# CSR8675_Module_Bluetooth_Speaker.net
KiCad netlist of a schematic drawn in EasyEDA Pro
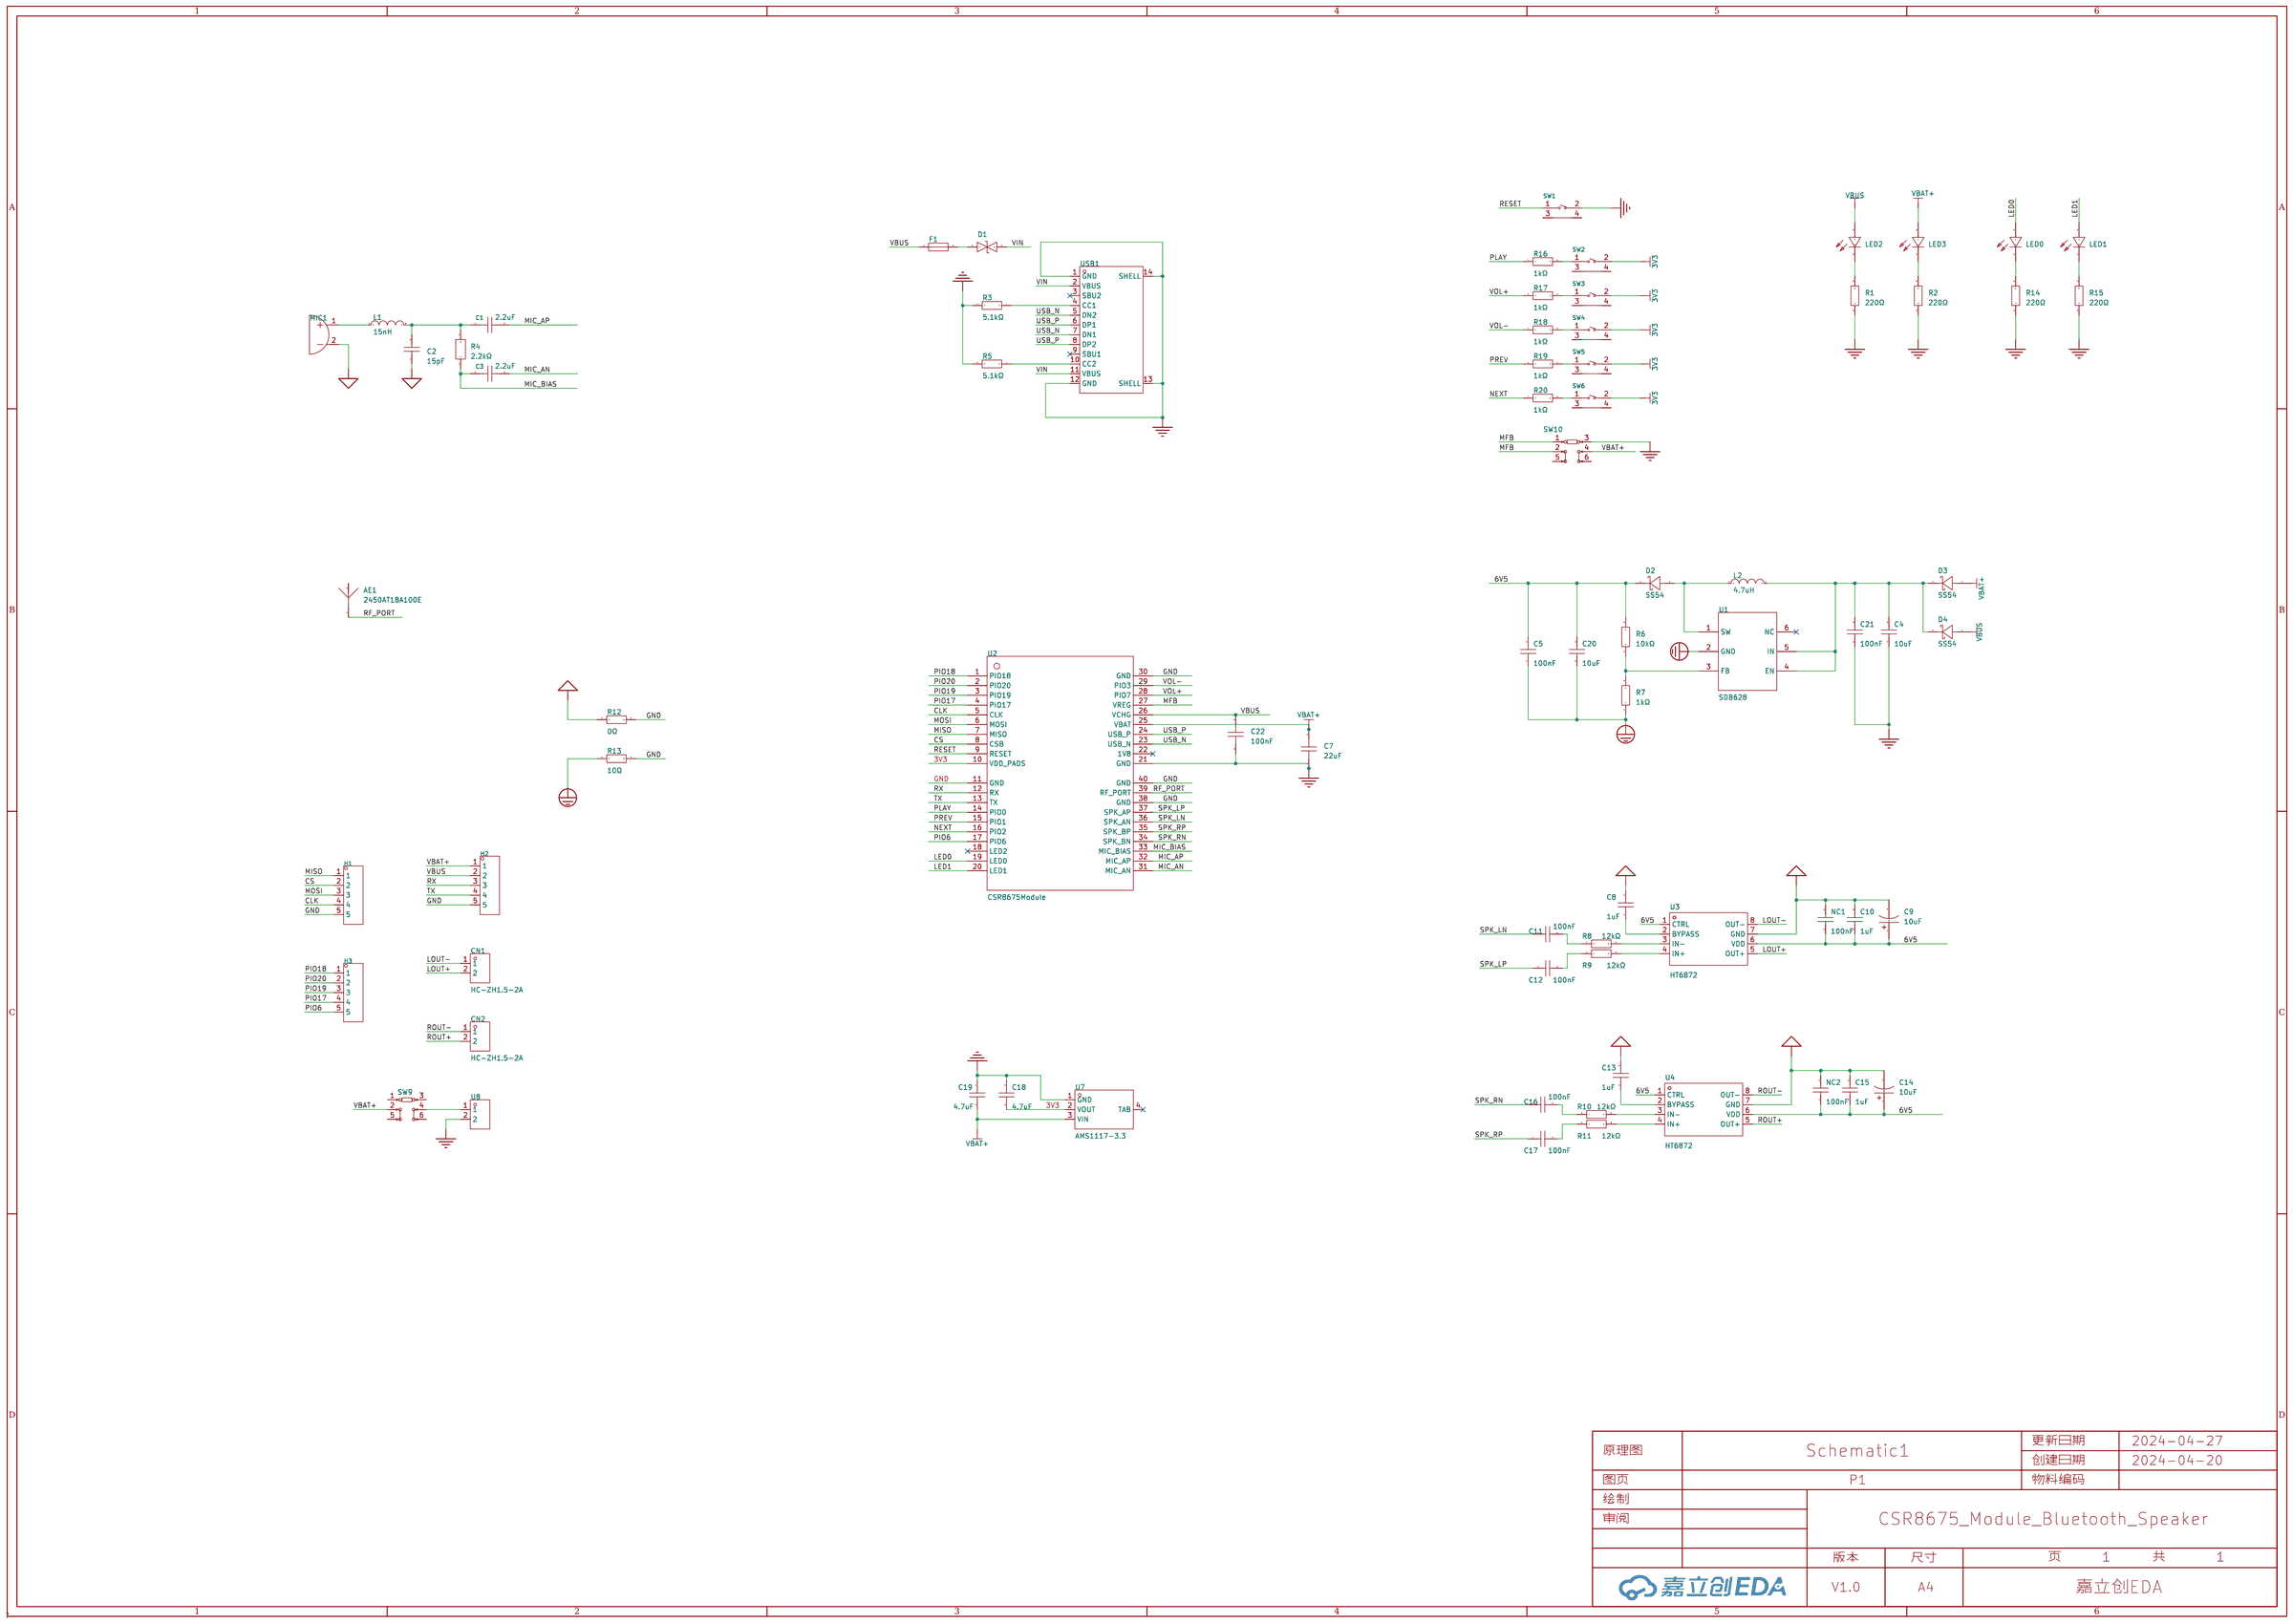
[diagram p0: schematic sheet]

(export (version "E")
  (design (tool "Eeschema 10.0.6"))
  (components
    (comp (ref "AE1")
      (value "2450AT18A100E")
      (footprint "easyedapro:ANT-SMD_L3.2-W1.6")
      (description "天线类型:2.4G天线;中心频点:2.4GHz;带宽:-;峰值增益:0.5dBi;极化方式:-;功率容量:2W;驻波比:-;")
      (fields (field (name "Manufacturer") "JOHANSON(约翰逊)"))
      (libsource (lib "easyedapro") (part "2450AT18A100E"))
    )
    (comp (ref "C1")
      (value "2.2uF")
      (footprint "easyedapro:C0603")
      (description "容值:2.2uF;精度:±10%;额定电压:50V;材质(温度系数):X5R;")
      (fields
        (field (name "Manufacturer Part") "CL10A225KB8NNNC")
        (field (name "Manufacturer") "SAMSUNG(三星)")
      )
      (libsource (lib "easyedapro") (part "CL10A225KB8NNNC"))
    )
    (comp (ref "C2")
      (value "15pF")
      (footprint "easyedapro:C0603")
      (description "容值:15pF;精度:±5%;额定电压:50V;材质(温度系数):NP0;")
      (fields
        (field (name "Manufacturer Part") "CC0603JRNPO9BN150")
        (field (name "Manufacturer") "YAGEO(国巨)")
      )
      (libsource (lib "easyedapro") (part "CC0603JRNPO9BN150"))
    )
    (comp (ref "C3")
      (value "2.2uF")
      (footprint "easyedapro:C0603")
      (description "容值:2.2uF;精度:±10%;额定电压:50V;材质(温度系数):X5R;")
      (fields
        (field (name "Manufacturer Part") "CL10A225KB8NNNC")
        (field (name "Manufacturer") "SAMSUNG(三星)")
      )
      (libsource (lib "easyedapro") (part "CL10A225KB8NNNC"))
    )
    (comp (ref "C4")
      (value "10uF")
      (footprint "easyedapro:C0603")
      (description "容值:1uF;精度:±10%;额定电压:50V;材质(温度系数):X5R;")
      (fields
        (field (name "Manufacturer Part") "CL10A105KB8NNNC")
        (field (name "Manufacturer") "SAMSUNG(三星)")
      )
      (libsource (lib "easyedapro") (part "CL10A105KB8NNNC"))
    )
    (comp (ref "C5")
      (value "100nF")
      (footprint "easyedapro:C0603")
      (description "容值:1uF;精度:±10%;额定电压:50V;材质(温度系数):X5R;")
      (fields
        (field (name "Manufacturer Part") "CL10A105KB8NNNC")
        (field (name "Manufacturer") "SAMSUNG(三星)")
      )
      (libsource (lib "easyedapro") (part "CL10A105KB8NNNC"))
    )
    (comp (ref "C7")
      (value "22uF")
      (footprint "easyedapro:c0805")
      (description "容值:22uF;精度:±20%;额定电压:25V;材质(温度系数):X5R;")
      (fields
        (field (name "Manufacturer Part") "CL21A226MAQNNNE")
        (field (name "Manufacturer") "SAMSUNG(三星)")
      )
      (libsource (lib "easyedapro") (part "CL21A226MAQNNNE"))
    )
    (comp (ref "C8")
      (value "1uF")
      (footprint "easyedapro:C0603")
      (description "容值:1uF;精度:±10%;额定电压:50V;材质(温度系数):X5R;")
      (fields
        (field (name "Manufacturer Part") "CL10A105KB8NNNC")
        (field (name "Manufacturer") "SAMSUNG(三星)")
      )
      (libsource (lib "easyedapro") (part "CL10A105KB8NNNC"))
    )
    (comp (ref "C9")
      (value "10uF")
      (footprint "easyedapro:CAP-TH_BD5.0-P2.00-D0.8-FD")
      (description "容值:10uF;精度:±20%;额定电压:50V;纹波电流:50mA@120Hz;等效串联电阻:-;")
      (fields
        (field (name "Manufacturer Part") "01EC1809SHC10UF50V")
        (field (name "Manufacturer") "KNSCHA(科尼盛)")
      )
      (libsource (lib "easyedapro") (part "01EC1809SHC10UF50V"))
    )
    (comp (ref "C10")
      (value "1uF")
      (footprint "easyedapro:C0603")
      (description "容值:1uF;精度:±10%;额定电压:50V;材质(温度系数):X5R;")
      (fields
        (field (name "Manufacturer Part") "CL10A105KB8NNNC")
        (field (name "Manufacturer") "SAMSUNG(三星)")
      )
      (libsource (lib "easyedapro") (part "CL10A105KB8NNNC"))
    )
    (comp (ref "C11")
      (value "100nF")
      (footprint "easyedapro:C0603")
      (description "容值:100nF;精度:±10%;额定电压:50V;材质(温度系数):X7R;")
      (fields (field (name "Manufacturer Part") "0603B104K500NT") (field (name "Manufacturer") "FH(风华)"))
      (libsource (lib "easyedapro") (part "0603B104K500NT"))
    )
    (comp (ref "C12")
      (value "100nF")
      (footprint "easyedapro:C0603")
      (description "容值:100nF;精度:±10%;额定电压:50V;材质(温度系数):X7R;")
      (fields (field (name "Manufacturer Part") "0603B104K500NT") (field (name "Manufacturer") "FH(风华)"))
      (libsource (lib "easyedapro") (part "0603B104K500NT"))
    )
    (comp (ref "C13")
      (value "1uF")
      (footprint "easyedapro:C0603")
      (description "容值:1uF;精度:±10%;额定电压:50V;材质(温度系数):X5R;")
      (fields
        (field (name "Manufacturer Part") "CL10A105KB8NNNC")
        (field (name "Manufacturer") "SAMSUNG(三星)")
      )
      (libsource (lib "easyedapro") (part "CL10A105KB8NNNC"))
    )
    (comp (ref "C14")
      (value "10uF")
      (footprint "easyedapro:CAP-TH_BD5.0-P2.00-D0.8-FD")
      (description "容值:10uF;精度:±20%;额定电压:50V;纹波电流:50mA@120Hz;等效串联电阻:-;")
      (fields
        (field (name "Manufacturer Part") "01EC1809SHC10UF50V")
        (field (name "Manufacturer") "KNSCHA(科尼盛)")
      )
      (libsource (lib "easyedapro") (part "01EC1809SHC10UF50V"))
    )
    (comp (ref "C15")
      (value "1uF")
      (footprint "easyedapro:C0603")
      (description "容值:1uF;精度:±10%;额定电压:50V;材质(温度系数):X5R;")
      (fields
        (field (name "Manufacturer Part") "CL10A105KB8NNNC")
        (field (name "Manufacturer") "SAMSUNG(三星)")
      )
      (libsource (lib "easyedapro") (part "CL10A105KB8NNNC"))
    )
    (comp (ref "C16")
      (value "100nF")
      (footprint "easyedapro:C0603")
      (description "容值:100nF;精度:±10%;额定电压:50V;材质(温度系数):X7R;")
      (fields (field (name "Manufacturer Part") "0603B104K500NT") (field (name "Manufacturer") "FH(风华)"))
      (libsource (lib "easyedapro") (part "0603B104K500NT"))
    )
    (comp (ref "C17")
      (value "100nF")
      (footprint "easyedapro:C0603")
      (description "容值:100nF;精度:±10%;额定电压:50V;材质(温度系数):X7R;")
      (fields (field (name "Manufacturer Part") "0603B104K500NT") (field (name "Manufacturer") "FH(风华)"))
      (libsource (lib "easyedapro") (part "0603B104K500NT"))
    )
    (comp (ref "C18")
      (value "4.7uF")
      (footprint "easyedapro:c0805")
      (description "容值:4.7uF;精度:±10%;额定电压:25V;材质(温度系数):X5R;")
      (fields
        (field (name "Manufacturer Part") "CL21A475KAQNNNE")
        (field (name "Manufacturer") "SAMSUNG(三星)")
      )
      (libsource (lib "easyedapro") (part "CL21A475KAQNNNE"))
    )
    (comp (ref "C19")
      (value "4.7uF")
      (footprint "easyedapro:c0805")
      (description "容值:4.7uF;精度:±10%;额定电压:25V;材质(温度系数):X5R;")
      (fields
        (field (name "Manufacturer Part") "CL21A475KAQNNNE")
        (field (name "Manufacturer") "SAMSUNG(三星)")
      )
      (libsource (lib "easyedapro") (part "CL21A475KAQNNNE"))
    )
    (comp (ref "C20")
      (value "10uF")
      (footprint "easyedapro:C0603")
      (description "容值:1uF;精度:±10%;额定电压:50V;材质(温度系数):X5R;")
      (fields
        (field (name "Manufacturer Part") "CL10A105KB8NNNC")
        (field (name "Manufacturer") "SAMSUNG(三星)")
      )
      (libsource (lib "easyedapro") (part "CL10A105KB8NNNC"))
    )
    (comp (ref "C21")
      (value "100nF")
      (footprint "easyedapro:C0603")
      (description "容值:1uF;精度:±10%;额定电压:50V;材质(温度系数):X5R;")
      (fields
        (field (name "Manufacturer Part") "CL10A105KB8NNNC")
        (field (name "Manufacturer") "SAMSUNG(三星)")
      )
      (libsource (lib "easyedapro") (part "CL10A105KB8NNNC"))
    )
    (comp (ref "C22")
      (value "100nF")
      (footprint "easyedapro:C0603")
      (description "容值:100nF;精度:±10%;额定电压:50V;材质(温度系数):X7R;")
      (fields
        (field (name "Manufacturer Part") "CC0603KRX7R9BB104")
        (field (name "Manufacturer") "YAGEO(国巨)")
      )
      (libsource (lib "easyedapro") (part "CC0603KRX7R9BB104"))
    )
    (comp (ref "CN1")
      (value "HC-ZH1.5-2A")
      (footprint "easyedapro:CONN-TH_2P-P1.50_HCTL_HC-ZH1.5-2A")
      (fields (field (name "Manufacturer") "HCTL(华灿天禄)"))
      (libsource (lib "easyedapro") (part "HC-ZH1.5-2A"))
    )
    (comp (ref "CN2")
      (value "HC-ZH1.5-2A")
      (footprint "easyedapro:CONN-TH_2P-P1.50_HCTL_HC-ZH1.5-2A")
      (fields (field (name "Manufacturer") "HCTL(华灿天禄)"))
      (libsource (lib "easyedapro") (part "HC-ZH1.5-2A"))
    )
    (comp (ref "D1")
      (value "0603ESDA-05N")
      (footprint "easyedapro:D0603-BI")
      (description "极性:双向;反向截止电压(Vrwm):5V;最大钳位电压:50V;")
      (fields (field (name "Manufacturer") "BORN(伯恩半导体)"))
      (libsource (lib "easyedapro") (part "0603ESDA-05N"))
    )
    (comp (ref "D2")
      (value "SS54")
      (footprint "easyedapro:SMA_L4.3-W2.6-LS5.0-FD")
      (description "二极管配置:独立式;正向压降(Vf):550mV@5.0A;直流反向耐压(Vr):40V;平均整流电流(Io):5A;")
      (fields (field (name "Manufacturer") "宏迦橙"))
      (libsource (lib "easyedapro") (part "SS54_C7420369"))
    )
    (comp (ref "D3")
      (value "SS54")
      (footprint "easyedapro:SMA_L4.3-W2.6-LS5.0-FD")
      (description "二极管配置:独立式;正向压降(Vf):550mV@5.0A;直流反向耐压(Vr):40V;平均整流电流(Io):5A;")
      (fields (field (name "Manufacturer") "宏迦橙"))
      (libsource (lib "easyedapro") (part "SS54_C7420369"))
    )
    (comp (ref "D4")
      (value "SS54")
      (footprint "easyedapro:SMA_L4.3-W2.6-LS5.0-FD")
      (description "二极管配置:独立式;正向压降(Vf):550mV@5.0A;直流反向耐压(Vr):40V;平均整流电流(Io):5A;")
      (fields (field (name "Manufacturer") "宏迦橙"))
      (libsource (lib "easyedapro") (part "SS54_C7420369"))
    )
    (comp (ref "F1")
      (value "BSMD1210L-500")
      (footprint "easyedapro:F1210")
      (description "最大电压:6V;最大电流:50A;保持电流:5A;跳闸电流:10A;")
      (fields (field (name "Manufacturer") "BHFUSE(佰宏)"))
      (libsource (lib "easyedapro") (part "BSMD1210L-500"))
    )
    (comp (ref "H1")
      (value "~")
      (footprint "easyedapro:HDR-TH_5P-P2.54-V-M")
      (libsource (lib "easyedapro") (part "MTP125-1105S1"))
    )
    (comp (ref "H2")
      (value "~")
      (footprint "easyedapro:HDR-TH_5P-P2.54-V-M")
      (libsource (lib "easyedapro") (part "MTP125-1105S1"))
    )
    (comp (ref "H3")
      (value "~")
      (footprint "easyedapro:HDR-TH_5P-P2.54-V-M")
      (libsource (lib "easyedapro") (part "MTP125-1105S1"))
    )
    (comp (ref "L1")
      (value "15nH")
      (footprint "easyedapro:L0805")
      (description "电感值:15nH;精度:±5%;额定电流:300mA;饱和电流(Isat):-;直流电阻(DCR):400mΩ;")
      (fields (field (name "Manufacturer Part") "VHF201209H15NJT") (field (name "Manufacturer") "FH(风华)"))
      (libsource (lib "easyedapro") (part "VHF201209H15NJT"))
    )
    (comp (ref "L2")
      (value "4.7uH")
      (footprint "easyedapro:IND-SMD_L4.4-W4.2")
      (description "电感值:4.7uH;精度:±20%;额定电流:2.8A;饱和电流(Isat):3A;类型:一体成型电感;")
      (fields (field (name "Manufacturer Part") "FXL0420-4R7-M") (field (name "Manufacturer") "cjiang(长江微电)"))
      (libsource (lib "easyedapro") (part "FXL0420-4R7-M"))
    )
    (comp (ref "LED0")
      (value "NCD0603R1")
      (footprint "easyedapro:LED0603-RD_RED")
      (fields (field (name "Manufacturer") "国星光电"))
      (libsource (lib "easyedapro") (part "FC-DA1608HRK-620D"))
    )
    (comp (ref "LED1")
      (value "NCD0603R1")
      (footprint "easyedapro:LED0603-RD_RED")
      (fields (field (name "Manufacturer") "国星光电"))
      (libsource (lib "easyedapro") (part "FC-DA1608HRK-620D"))
    )
    (comp (ref "LED2")
      (value "NCD0603R1")
      (footprint "easyedapro:LED0603-RD_RED")
      (fields (field (name "Manufacturer") "国星光电"))
      (libsource (lib "easyedapro") (part "FC-DA1608HRK-620D"))
    )
    (comp (ref "LED3")
      (value "NCD0603R1")
      (footprint "easyedapro:LED0603-RD_RED")
      (fields (field (name "Manufacturer") "国星光电"))
      (libsource (lib "easyedapro") (part "FC-DA1608HRK-620D"))
    )
    (comp (ref "MIC1")
      (value "GMI6027P-34DB")
      (footprint "easyedapro:MIC-TH_BD6.0-P1.90-D0.4-L")
      (fields (field (name "Manufacturer") "INGHAi(赢海)"))
      (libsource (lib "easyedapro") (part "GMI6027P-34DB"))
    )
    (comp (ref "NC1")
      (value "100nF")
      (footprint "easyedapro:C0603")
      (description "容值:10nF;精度:±10%;额定电压:50V;材质(温度系数):X7R;")
      (fields
        (field (name "Manufacturer Part") "CC0603KRX7R9BB103")
        (field (name "Manufacturer") "YAGEO(国巨)")
      )
      (libsource (lib "easyedapro") (part "CC0603KRX7R9BB103"))
    )
    (comp (ref "NC2")
      (value "100nF")
      (footprint "easyedapro:C0603")
      (description "容值:10nF;精度:±10%;额定电压:50V;材质(温度系数):X7R;")
      (fields
        (field (name "Manufacturer Part") "CC0603KRX7R9BB103")
        (field (name "Manufacturer") "YAGEO(国巨)")
      )
      (libsource (lib "easyedapro") (part "CC0603KRX7R9BB103"))
    )
    (comp (ref "R1")
      (value "220Ω")
      (footprint "easyedapro:R0603")
      (description "电阻类型:厚膜电阻;阻值:220Ω;精度:±5%;功率:100mW;最大工作电压:75V;温度系数:±100ppm/°C;")
      (fields
        (field (name "Manufacturer Part") "0603WAJ0221T5E")
        (field (name "Manufacturer") "UNI-ROYAL(厚声)")
      )
      (libsource (lib "easyedapro") (part "0603WAJ0221T5E"))
    )
    (comp (ref "R2")
      (value "220Ω")
      (footprint "easyedapro:R0603")
      (description "电阻类型:厚膜电阻;阻值:220Ω;精度:±5%;功率:100mW;最大工作电压:75V;温度系数:±100ppm/°C;")
      (fields
        (field (name "Manufacturer Part") "0603WAJ0221T5E")
        (field (name "Manufacturer") "UNI-ROYAL(厚声)")
      )
      (libsource (lib "easyedapro") (part "0603WAJ0221T5E"))
    )
    (comp (ref "R3")
      (value "5.1kΩ")
      (footprint "easyedapro:R0603")
      (description "电阻类型:厚膜电阻;阻值:5.1kΩ;精度:±1%;功率:100mW;最大工作电压:75V;温度系数:±100ppm/°C;")
      (fields
        (field (name "Manufacturer Part") "0603WAF5101T5E")
        (field (name "Manufacturer") "UNI-ROYAL(厚声)")
      )
      (libsource (lib "easyedapro") (part "0603WAF5101T5E"))
    )
    (comp (ref "R4")
      (value "2.2kΩ")
      (footprint "easyedapro:R0603")
      (description "电阻类型:厚膜电阻;阻值:2.2kΩ;精度:±5%;功率:100mW;最大工作电压:75V;温度系数:±100ppm/°C;")
      (fields (field (name "Manufacturer Part") "FRC0603J222 TS") (field (name "Manufacturer") "FOJAN(富捷)"))
      (libsource (lib "easyedapro") (part "FRC0603J222 TS"))
    )
    (comp (ref "R5")
      (value "5.1kΩ")
      (footprint "easyedapro:R0603")
      (description "电阻类型:厚膜电阻;阻值:5.1kΩ;精度:±1%;功率:100mW;最大工作电压:75V;温度系数:±100ppm/°C;")
      (fields
        (field (name "Manufacturer Part") "0603WAF5101T5E")
        (field (name "Manufacturer") "UNI-ROYAL(厚声)")
      )
      (libsource (lib "easyedapro") (part "0603WAF5101T5E"))
    )
    (comp (ref "R6")
      (value "10kΩ")
      (footprint "easyedapro:R0603")
      (description "电阻类型:厚膜电阻;阻值:10kΩ;精度:±1%;功率:100mW;最大工作电压:75V;温度系数:±100ppm/°C;")
      (fields
        (field (name "Manufacturer Part") "0603WAF1002T5E")
        (field (name "Manufacturer") "UNI-ROYAL(厚声)")
      )
      (libsource (lib "easyedapro") (part "0603WAF1002T5E"))
    )
    (comp (ref "R7")
      (value "1kΩ")
      (footprint "easyedapro:R0603")
      (description "电阻类型:厚膜电阻;阻值:1kΩ;精度:±1%;功率:100mW;最大工作电压:75V;温度系数:±100ppm/°C;")
      (fields (field (name "Manufacturer Part") "RC0603FR-071KL") (field (name "Manufacturer") "YAGEO(国巨)"))
      (libsource (lib "easyedapro") (part "RC0603FR-071KL"))
    )
    (comp (ref "R8")
      (value "12kΩ")
      (footprint "easyedapro:R0603")
      (description "电阻类型:厚膜电阻;阻值:12kΩ;精度:±1%;功率:100mW;最大工作电压:75V;温度系数:±100ppm/°C;")
      (fields
        (field (name "Manufacturer Part") "0603WAF1202T5E")
        (field (name "Manufacturer") "UNI-ROYAL(厚声)")
      )
      (libsource (lib "easyedapro") (part "0603WAF1202T5E"))
    )
    (comp (ref "R9")
      (value "12kΩ")
      (footprint "easyedapro:R0603")
      (description "电阻类型:厚膜电阻;阻值:12kΩ;精度:±1%;功率:100mW;最大工作电压:75V;温度系数:±100ppm/°C;")
      (fields
        (field (name "Manufacturer Part") "0603WAF1202T5E")
        (field (name "Manufacturer") "UNI-ROYAL(厚声)")
      )
      (libsource (lib "easyedapro") (part "0603WAF1202T5E"))
    )
    (comp (ref "R10")
      (value "12kΩ")
      (footprint "easyedapro:R0603")
      (description "电阻类型:厚膜电阻;阻值:12kΩ;精度:±1%;功率:100mW;最大工作电压:75V;温度系数:±100ppm/°C;")
      (fields
        (field (name "Manufacturer Part") "0603WAF1202T5E")
        (field (name "Manufacturer") "UNI-ROYAL(厚声)")
      )
      (libsource (lib "easyedapro") (part "0603WAF1202T5E"))
    )
    (comp (ref "R11")
      (value "12kΩ")
      (footprint "easyedapro:R0603")
      (description "电阻类型:厚膜电阻;阻值:12kΩ;精度:±1%;功率:100mW;最大工作电压:75V;温度系数:±100ppm/°C;")
      (fields
        (field (name "Manufacturer Part") "0603WAF1202T5E")
        (field (name "Manufacturer") "UNI-ROYAL(厚声)")
      )
      (libsource (lib "easyedapro") (part "0603WAF1202T5E"))
    )
    (comp (ref "R12")
      (value "0Ω")
      (footprint "easyedapro:R0603")
      (description "电阻类型:厚膜电阻;阻值:0Ω;精度:±1%;功率:100mW;最大工作电压:75V;")
      (fields
        (field (name "Manufacturer Part") "0603WAF0000T5E")
        (field (name "Manufacturer") "UNI-ROYAL(厚声)")
      )
      (libsource (lib "easyedapro") (part "0603WAF0000T5E"))
    )
    (comp (ref "R13")
      (value "10Ω")
      (footprint "easyedapro:R0603")
      (description "电阻类型:厚膜电阻;阻值:0Ω;精度:±1%;功率:100mW;最大工作电压:75V;")
      (fields
        (field (name "Manufacturer Part") "0603WAF0000T5E")
        (field (name "Manufacturer") "UNI-ROYAL(厚声)")
      )
      (libsource (lib "easyedapro") (part "0603WAF0000T5E"))
    )
    (comp (ref "R14")
      (value "220Ω")
      (footprint "easyedapro:R0603")
      (description "电阻类型:厚膜电阻;阻值:220Ω;精度:±5%;功率:100mW;最大工作电压:75V;温度系数:±100ppm/°C;")
      (fields
        (field (name "Manufacturer Part") "0603WAJ0221T5E")
        (field (name "Manufacturer") "UNI-ROYAL(厚声)")
      )
      (libsource (lib "easyedapro") (part "0603WAJ0221T5E"))
    )
    (comp (ref "R15")
      (value "220Ω")
      (footprint "easyedapro:R0603")
      (description "电阻类型:厚膜电阻;阻值:220Ω;精度:±5%;功率:100mW;最大工作电压:75V;温度系数:±100ppm/°C;")
      (fields
        (field (name "Manufacturer Part") "0603WAJ0221T5E")
        (field (name "Manufacturer") "UNI-ROYAL(厚声)")
      )
      (libsource (lib "easyedapro") (part "0603WAJ0221T5E"))
    )
    (comp (ref "R16")
      (value "1kΩ")
      (footprint "easyedapro:R0603")
      (description "电阻类型:厚膜电阻;阻值:1kΩ;精度:±1%;功率:100mW;最大工作电压:75V;温度系数:±100ppm/°C;")
      (fields (field (name "Manufacturer Part") "RC0603FR-071KL") (field (name "Manufacturer") "YAGEO(国巨)"))
      (libsource (lib "easyedapro") (part "RC0603FR-071KL"))
    )
    (comp (ref "R17")
      (value "1kΩ")
      (footprint "easyedapro:R0603")
      (description "电阻类型:厚膜电阻;阻值:1kΩ;精度:±1%;功率:100mW;最大工作电压:75V;温度系数:±100ppm/°C;")
      (fields (field (name "Manufacturer Part") "RC0603FR-071KL") (field (name "Manufacturer") "YAGEO(国巨)"))
      (libsource (lib "easyedapro") (part "RC0603FR-071KL"))
    )
    (comp (ref "R18")
      (value "1kΩ")
      (footprint "easyedapro:R0603")
      (description "电阻类型:厚膜电阻;阻值:1kΩ;精度:±1%;功率:100mW;最大工作电压:75V;温度系数:±100ppm/°C;")
      (fields (field (name "Manufacturer Part") "RC0603FR-071KL") (field (name "Manufacturer") "YAGEO(国巨)"))
      (libsource (lib "easyedapro") (part "RC0603FR-071KL"))
    )
    (comp (ref "R19")
      (value "1kΩ")
      (footprint "easyedapro:R0603")
      (description "电阻类型:厚膜电阻;阻值:1kΩ;精度:±1%;功率:100mW;最大工作电压:75V;温度系数:±100ppm/°C;")
      (fields (field (name "Manufacturer Part") "RC0603FR-071KL") (field (name "Manufacturer") "YAGEO(国巨)"))
      (libsource (lib "easyedapro") (part "RC0603FR-071KL"))
    )
    (comp (ref "R20")
      (value "1kΩ")
      (footprint "easyedapro:R0603")
      (description "电阻类型:厚膜电阻;阻值:1kΩ;精度:±1%;功率:100mW;最大工作电压:75V;温度系数:±100ppm/°C;")
      (fields (field (name "Manufacturer Part") "RC0603FR-071KL") (field (name "Manufacturer") "YAGEO(国巨)"))
      (libsource (lib "easyedapro") (part "RC0603FR-071KL"))
    )
    (comp (ref "SW1")
      (value "TC-6615-5-260G")
      (footprint "easyedapro:SW-TH_4P-L7.5-W5.0-P4.50")
      (fields (field (name "Manufacturer") "HCTL(华灿天禄)"))
      (libsource (lib "easyedapro") (part "TC-6615-5-260G"))
    )
    (comp (ref "SW2")
      (value "TC-6615-5-260G")
      (footprint "easyedapro:SW-TH_4P-L7.5-W5.0-P4.50")
      (fields (field (name "Manufacturer") "HCTL(华灿天禄)"))
      (libsource (lib "easyedapro") (part "TC-6615-5-260G"))
    )
    (comp (ref "SW3")
      (value "TC-6615-5-260G")
      (footprint "easyedapro:SW-TH_4P-L7.5-W5.0-P4.50")
      (fields (field (name "Manufacturer") "HCTL(华灿天禄)"))
      (libsource (lib "easyedapro") (part "TC-6615-5-260G"))
    )
    (comp (ref "SW4")
      (value "TC-6615-5-260G")
      (footprint "easyedapro:SW-TH_4P-L7.5-W5.0-P4.50")
      (fields (field (name "Manufacturer") "HCTL(华灿天禄)"))
      (libsource (lib "easyedapro") (part "TC-6615-5-260G"))
    )
    (comp (ref "SW5")
      (value "TC-6615-5-260G")
      (footprint "easyedapro:SW-TH_4P-L7.5-W5.0-P4.50")
      (fields (field (name "Manufacturer") "HCTL(华灿天禄)"))
      (libsource (lib "easyedapro") (part "TC-6615-5-260G"))
    )
    (comp (ref "SW6")
      (value "TC-6615-5-260G")
      (footprint "easyedapro:SW-TH_4P-L7.5-W5.0-P4.50")
      (fields (field (name "Manufacturer") "HCTL(华灿天禄)"))
      (libsource (lib "easyedapro") (part "TC-6615-5-260G"))
    )
    (comp (ref "SW9")
      (value "XKB5858-Z-E")
      (footprint "easyedapro:SW-TH_XKB5858-Z-E")
      (description "自锁/无锁:自锁;安装方式:卧插;触点电流:100mA;额定电压 (AC):250V;额定电压 (DC):30V;带灯:不带;作用力:250gf;机械寿命:10万次;")
      (fields (field (name "Manufacturer") "XKB Connectivity(中国星坤)"))
      (libsource (lib "easyedapro") (part "XKB5858-Z-E"))
    )
    (comp (ref "SW10")
      (value "XKB5858-Z-E")
      (footprint "easyedapro:SW-TH_XKB5858-Z-E")
      (description "自锁/无锁:自锁;安装方式:卧插;触点电流:100mA;额定电压 (AC):250V;额定电压 (DC):30V;带灯:不带;作用力:250gf;机械寿命:10万次;")
      (fields (field (name "Manufacturer") "XKB Connectivity(中国星坤)"))
      (libsource (lib "easyedapro") (part "XKB5858-Z-E"))
    )
    (comp (ref "U1")
      (value "SDB628")
      (footprint "easyedapro:SOT-23-6_L2.9-W1.6-P0.95-LS2.8-BR")
      (description "功能类型:升压型;输入电压:2V~24V;输出电压:28V;输出电流(最大值):2A;")
      (fields (field (name "Manufacturer") "SHOUDING(首鼎半导体)"))
      (libsource (lib "easyedapro") (part "SDB628"))
    )
    (comp (ref "U2")
      (value "CSR8675Module")
      (footprint "easyedapro:CSR8675Module")
      (description "蓝牙库")
      (libsource (lib "easyedapro") (part "CSR8675module"))
    )
    (comp (ref "U3")
      (value "HT6872")
      (footprint "easyedapro:SOP-8_L4.9-W3.9-P1.27-LS6.0-BL")
      (description "功放类型:D类功放;扬声器通道数:单声道;输出功率:3.85Wx1@4Ω;")
      (fields (field (name "Manufacturer") "嘉兴禾润"))
      (libsource (lib "easyedapro") (part "HT6872"))
    )
    (comp (ref "U4")
      (value "HT6872")
      (footprint "easyedapro:SOP-8_L4.9-W3.9-P1.27-LS6.0-BL")
      (description "功放类型:D类功放;扬声器通道数:单声道;输出功率:3.85Wx1@4Ω;")
      (fields (field (name "Manufacturer") "嘉兴禾润"))
      (libsource (lib "easyedapro") (part "HT6872"))
    )
    (comp (ref "U7")
      (value "AMS1117-3.3")
      (footprint "easyedapro:SOT-223-3_L6.5-W3.5-P3.05-LS7.0")
      (description "输出类型：固定 输出极性：正 最大输入电压：18V 输出电压：3.3V 输出电流：1A 电源纹波抑制比(PSRR)：60dB@(120Hz)。当前应用较多领域：三端稳压器，机顶盒")
      (fields (field (name "Manufacturer") "TWGMC(台湾迪嘉)"))
      (libsource (lib "easyedapro") (part "AMS1117-3.3_C5250992"))
    )
    (comp (ref "U8")
      (value "WAFER-XH254Z-2A")
      (footprint "easyedapro:CONN-TH_2P-P2.50_XH-2A_3045048")
      (description "插针结构:1x2P;间距:2.54mm;安装方式:直插;参考系列:XH;总PIN数:2P;排数:1;每排PIN数:2;额定电流:3A;工作温度范围:-25°C~+85°C;")
      (fields (field (name "Manufacturer") "HANBO(汉博)"))
      (libsource (lib "easyedapro") (part "WAFER-XH254Z-2A"))
    )
    (comp (ref "USB1")
      (value "TYPE-C 16PIN 2MD(073)")
      (footprint "easyedapro:USB-C-SMD_TYPE-C-6PIN-2MD-073")
      (description "连接器类型:Type-C;标准:-;公母:母;端口数量:1;触点数量:16P;安装方式:卧贴;额定电流 - 电源:5A;工作温度范围:-25°C~+85°C;")
      (fields (field (name "Manufacturer") "SHOU HAN(首韩)"))
      (libsource (lib "easyedapro") (part "TYPE-C 16PIN 2MD(073)"))
    )
  )
  (nets
    (net (code "1") (name "/6V5") (class "Default")
      (node (ref "C10") (pin "1") (pinfunction "1_1") (pintype "input"))
      (node (ref "C14") (pin "1") (pinfunction "1_1") (pintype "unspecified"))
      (node (ref "C15") (pin "1") (pinfunction "1_1") (pintype "input"))
      (node (ref "C20") (pin "2") (pinfunction "2_2") (pintype "input"))
      (node (ref "C5") (pin "2") (pinfunction "2_2") (pintype "input"))
      (node (ref "C9") (pin "1") (pinfunction "1_1") (pintype "unspecified"))
      (node (ref "D2") (pin "2") (pinfunction "K_2") (pintype "unspecified"))
      (node (ref "NC1") (pin "1") (pinfunction "1_1") (pintype "input"))
      (node (ref "NC2") (pin "1") (pinfunction "1_1") (pintype "input"))
      (node (ref "R6") (pin "2") (pinfunction "2_2") (pintype "input"))
      (node (ref "U3") (pin "1") (pinfunction "CTRL_1") (pintype "unspecified"))
      (node (ref "U3") (pin "6") (pinfunction "VDD_6") (pintype "unspecified"))
      (node (ref "U4") (pin "1") (pinfunction "CTRL_1") (pintype "unspecified"))
      (node (ref "U4") (pin "6") (pinfunction "VDD_6") (pintype "unspecified"))
    )
    (net (code "2") (name "/CLK") (class "Default")
      (node (ref "H1") (pin "4") (pinfunction "4_4") (pintype "input"))
      (node (ref "U2") (pin "5") (pinfunction "CLK_5") (pintype "input"))
    )
    (net (code "3") (name "/CS") (class "Default")
      (node (ref "H1") (pin "2") (pinfunction "2_2") (pintype "input"))
      (node (ref "U2") (pin "8") (pinfunction "CSB_8") (pintype "input"))
    )
    (net (code "4") (name "/LED0") (class "Default")
      (node (ref "LED0") (pin "2") (pinfunction "A_2") (pintype "input"))
      (node (ref "U2") (pin "19") (pinfunction "LED0_19") (pintype "input"))
    )
    (net (code "5") (name "/LED1") (class "Default")
      (node (ref "LED1") (pin "2") (pinfunction "A_2") (pintype "input"))
      (node (ref "U2") (pin "20") (pinfunction "LED1_20") (pintype "input"))
    )
    (net (code "6") (name "/LOUT+") (class "Default")
      (node (ref "CN1") (pin "2") (pinfunction "2_2") (pintype "unspecified"))
      (node (ref "U3") (pin "5") (pinfunction "OUT+_5") (pintype "unspecified"))
    )
    (net (code "7") (name "/LOUT-") (class "Default")
      (node (ref "CN1") (pin "1") (pinfunction "1_1") (pintype "unspecified"))
      (node (ref "U3") (pin "8") (pinfunction "OUT-_8") (pintype "unspecified"))
    )
    (net (code "8") (name "/MFB") (class "Default")
      (node (ref "SW10") (pin "1") (pinfunction "1_1") (pintype "unspecified"))
      (node (ref "SW10") (pin "2") (pinfunction "2_2") (pintype "unspecified"))
      (node (ref "U2") (pin "27") (pinfunction "VREG_27") (pintype "input"))
    )
    (net (code "9") (name "/MIC_AN") (class "Default")
      (node (ref "C3") (pin "2") (pinfunction "2_2") (pintype "input"))
      (node (ref "U2") (pin "31") (pinfunction "MIC_AN_31") (pintype "input"))
    )
    (net (code "10") (name "/MIC_AP") (class "Default")
      (node (ref "C1") (pin "2") (pinfunction "2_2") (pintype "input"))
      (node (ref "U2") (pin "32") (pinfunction "MIC_AP_32") (pintype "input"))
    )
    (net (code "11") (name "/MIC_BIAS") (class "Default")
      (node (ref "C3") (pin "1") (pinfunction "1_1") (pintype "input"))
      (node (ref "R4") (pin "1") (pinfunction "1_1") (pintype "unspecified"))
      (node (ref "U2") (pin "33") (pinfunction "MIC_BIAS_33") (pintype "input"))
    )
    (net (code "12") (name "/MISO") (class "Default")
      (node (ref "H1") (pin "1") (pinfunction "1_1") (pintype "input"))
      (node (ref "U2") (pin "7") (pinfunction "MISO_7") (pintype "input"))
    )
    (net (code "13") (name "/MOSI") (class "Default")
      (node (ref "H1") (pin "3") (pinfunction "3_3") (pintype "input"))
      (node (ref "U2") (pin "6") (pinfunction "MOSI_6") (pintype "input"))
    )
    (net (code "14") (name "/NEXT") (class "Default")
      (node (ref "R20") (pin "1") (pinfunction "1_1") (pintype "input"))
      (node (ref "U2") (pin "16") (pinfunction "PIO2_16") (pintype "input"))
    )
    (net (code "15") (name "/PIO6") (class "Default")
      (node (ref "H3") (pin "5") (pinfunction "5_5") (pintype "input"))
      (node (ref "U2") (pin "17") (pinfunction "PIO6_17") (pintype "input"))
    )
    (net (code "16") (name "/PIO17") (class "Default")
      (node (ref "H3") (pin "4") (pinfunction "4_4") (pintype "input"))
      (node (ref "U2") (pin "4") (pinfunction "PIO17_4") (pintype "input"))
    )
    (net (code "17") (name "/PIO18") (class "Default")
      (node (ref "H3") (pin "1") (pinfunction "1_1") (pintype "input"))
      (node (ref "U2") (pin "1") (pinfunction "PIO18_1") (pintype "input"))
    )
    (net (code "18") (name "/PIO19") (class "Default")
      (node (ref "H3") (pin "3") (pinfunction "3_3") (pintype "input"))
      (node (ref "U2") (pin "3") (pinfunction "PIO19_3") (pintype "input"))
    )
    (net (code "19") (name "/PIO20") (class "Default")
      (node (ref "H3") (pin "2") (pinfunction "2_2") (pintype "input"))
      (node (ref "U2") (pin "2") (pinfunction "PIO20_2") (pintype "input"))
    )
    (net (code "20") (name "/PLAY") (class "Default")
      (node (ref "R16") (pin "1") (pinfunction "1_1") (pintype "input"))
      (node (ref "U2") (pin "14") (pinfunction "PIO0_14") (pintype "input"))
    )
    (net (code "21") (name "/PREV") (class "Default")
      (node (ref "R19") (pin "1") (pinfunction "1_1") (pintype "input"))
      (node (ref "U2") (pin "15") (pinfunction "PIO1_15") (pintype "input"))
    )
    (net (code "22") (name "/RESET") (class "Default")
      (node (ref "SW1") (pin "1") (pinfunction "1_1") (pintype "input"))
      (node (ref "U2") (pin "9") (pinfunction "RESET_9") (pintype "input"))
    )
    (net (code "23") (name "/RF_PORT") (class "Default")
      (node (ref "AE1") (pin "1") (pinfunction "ANT_1") (pintype "input"))
      (node (ref "U2") (pin "39") (pinfunction "RF_PORT_39") (pintype "input"))
    )
    (net (code "24") (name "/ROUT+") (class "Default")
      (node (ref "CN2") (pin "2") (pinfunction "2_2") (pintype "unspecified"))
      (node (ref "U4") (pin "5") (pinfunction "OUT+_5") (pintype "unspecified"))
    )
    (net (code "25") (name "/ROUT-") (class "Default")
      (node (ref "CN2") (pin "1") (pinfunction "1_1") (pintype "unspecified"))
      (node (ref "U4") (pin "8") (pinfunction "OUT-_8") (pintype "unspecified"))
    )
    (net (code "26") (name "/RX") (class "Default")
      (node (ref "H2") (pin "3") (pinfunction "3_3") (pintype "input"))
      (node (ref "U2") (pin "12") (pinfunction "RX_12") (pintype "input"))
    )
    (net (code "27") (name "/SPK_LN") (class "Default")
      (node (ref "C11") (pin "1") (pinfunction "1_1") (pintype "input"))
      (node (ref "U2") (pin "36") (pinfunction "SPK_AN_36") (pintype "input"))
    )
    (net (code "28") (name "/SPK_LP") (class "Default")
      (node (ref "C12") (pin "1") (pinfunction "1_1") (pintype "input"))
      (node (ref "U2") (pin "37") (pinfunction "SPK_AP_37") (pintype "input"))
    )
    (net (code "29") (name "/SPK_RN") (class "Default")
      (node (ref "C16") (pin "1") (pinfunction "1_1") (pintype "input"))
      (node (ref "U2") (pin "34") (pinfunction "SPK_BN_34") (pintype "input"))
    )
    (net (code "30") (name "/SPK_RP") (class "Default")
      (node (ref "C17") (pin "1") (pinfunction "1_1") (pintype "input"))
      (node (ref "U2") (pin "35") (pinfunction "SPK_BP_35") (pintype "input"))
    )
    (net (code "31") (name "/TX") (class "Default")
      (node (ref "H2") (pin "4") (pinfunction "4_4") (pintype "input"))
      (node (ref "U2") (pin "13") (pinfunction "TX_13") (pintype "input"))
    )
    (net (code "32") (name "/USB_N") (class "Default")
      (node (ref "U2") (pin "23") (pinfunction "USB_N_23") (pintype "input"))
      (node (ref "USB1") (pin "5") (pinfunction "DN2_5") (pintype "unspecified"))
      (node (ref "USB1") (pin "7") (pinfunction "DN1_7") (pintype "unspecified"))
    )
    (net (code "33") (name "/USB_P") (class "Default")
      (node (ref "U2") (pin "24") (pinfunction "USB_P_24") (pintype "input"))
      (node (ref "USB1") (pin "6") (pinfunction "DP1_6") (pintype "unspecified"))
      (node (ref "USB1") (pin "8") (pinfunction "DP2_8") (pintype "unspecified"))
    )
    (net (code "34") (name "/VIN") (class "Default")
      (node (ref "D1") (pin "2") (pinfunction "2_2") (pintype "unspecified"))
      (node (ref "USB1") (pin "11") (pinfunction "VBUS_11") (pintype "unspecified"))
      (node (ref "USB1") (pin "2") (pinfunction "VBUS_2") (pintype "unspecified"))
    )
    (net (code "35") (name "/VOL+") (class "Default")
      (node (ref "R17") (pin "1") (pinfunction "1_1") (pintype "input"))
      (node (ref "U2") (pin "28") (pinfunction "PIO7_28") (pintype "input"))
    )
    (net (code "36") (name "/VOL-") (class "Default")
      (node (ref "R18") (pin "1") (pinfunction "1_1") (pintype "input"))
      (node (ref "U2") (pin "29") (pinfunction "PIO3_29") (pintype "input"))
    )
    (net (code "37") (name "3V3") (class "Default")
      (node (ref "C18") (pin "2") (pinfunction "2_2") (pintype "input"))
      (node (ref "SW2") (pin "2") (pinfunction "2_2") (pintype "input"))
      (node (ref "SW3") (pin "2") (pinfunction "2_2") (pintype "input"))
      (node (ref "SW4") (pin "2") (pinfunction "2_2") (pintype "input"))
      (node (ref "SW5") (pin "2") (pinfunction "2_2") (pintype "input"))
      (node (ref "SW6") (pin "2") (pinfunction "2_2") (pintype "input"))
      (node (ref "U2") (pin "10") (pinfunction "VDD_PADS_10") (pintype "input"))
      (node (ref "U7") (pin "2") (pinfunction "VOUT_2") (pintype "unspecified"))
    )
    (net (code "38") (name "AGND") (class "Default")
      (node (ref "C10") (pin "2") (pinfunction "2_2") (pintype "input"))
      (node (ref "C13") (pin "2") (pinfunction "2_2") (pintype "input"))
      (node (ref "C14") (pin "2") (pinfunction "2_2") (pintype "unspecified"))
      (node (ref "C15") (pin "2") (pinfunction "2_2") (pintype "input"))
      (node (ref "C2") (pin "1") (pinfunction "1_1") (pintype "input"))
      (node (ref "C8") (pin "2") (pinfunction "2_2") (pintype "input"))
      (node (ref "C9") (pin "2") (pinfunction "2_2") (pintype "unspecified"))
      (node (ref "MIC1") (pin "2") (pinfunction "2_2") (pintype "input"))
      (node (ref "NC1") (pin "2") (pinfunction "2_2") (pintype "input"))
      (node (ref "NC2") (pin "2") (pinfunction "2_2") (pintype "input"))
      (node (ref "R12") (pin "1") (pinfunction "1_1") (pintype "input"))
      (node (ref "U3") (pin "7") (pinfunction "GND_7") (pintype "unspecified"))
      (node (ref "U4") (pin "7") (pinfunction "GND_7") (pintype "unspecified"))
    )
    (net (code "39") (name "GND") (class "Default")
      (node (ref "C18") (pin "1") (pinfunction "1_1") (pintype "input"))
      (node (ref "C19") (pin "1") (pinfunction "1_1") (pintype "input"))
      (node (ref "C21") (pin "1") (pinfunction "1_1") (pintype "input"))
      (node (ref "C22") (pin "1") (pinfunction "1_1") (pintype "unspecified"))
      (node (ref "C4") (pin "1") (pinfunction "1_1") (pintype "input"))
      (node (ref "C7") (pin "1") (pinfunction "1_1") (pintype "unspecified"))
      (node (ref "H1") (pin "5") (pinfunction "5_5") (pintype "input"))
      (node (ref "H2") (pin "5") (pinfunction "5_5") (pintype "input"))
      (node (ref "R1") (pin "1") (pinfunction "1_1") (pintype "input"))
      (node (ref "R12") (pin "2") (pinfunction "2_2") (pintype "input"))
      (node (ref "R13") (pin "2") (pinfunction "2_2") (pintype "input"))
      (node (ref "R14") (pin "1") (pinfunction "1_1") (pintype "input"))
      (node (ref "R15") (pin "1") (pinfunction "1_1") (pintype "input"))
      (node (ref "R2") (pin "1") (pinfunction "1_1") (pintype "input"))
      (node (ref "R3") (pin "2") (pinfunction "2_2") (pintype "input"))
      (node (ref "R5") (pin "2") (pinfunction "2_2") (pintype "input"))
      (node (ref "SW1") (pin "2") (pinfunction "2_2") (pintype "input"))
      (node (ref "SW10") (pin "3") (pinfunction "3_3") (pintype "unspecified"))
      (node (ref "U2") (pin "11") (pinfunction "GND_11") (pintype "input"))
      (node (ref "U2") (pin "21") (pinfunction "GND_21") (pintype "input"))
      (node (ref "U2") (pin "30") (pinfunction "GND_30") (pintype "input"))
      (node (ref "U2") (pin "38") (pinfunction "GND_38") (pintype "input"))
      (node (ref "U2") (pin "40") (pinfunction "GND_40") (pintype "input"))
      (node (ref "U7") (pin "1") (pinfunction "GND_1") (pintype "unspecified"))
      (node (ref "U8") (pin "2") (pinfunction "2_2") (pintype "unspecified"))
      (node (ref "USB1") (pin "1") (pinfunction "GND_1") (pintype "unspecified"))
      (node (ref "USB1") (pin "12") (pinfunction "GND_12") (pintype "unspecified"))
      (node (ref "USB1") (pin "13") (pinfunction "SHELL_13") (pintype "unspecified"))
      (node (ref "USB1") (pin "14") (pinfunction "SHELL_14") (pintype "unspecified"))
    )
    (net (code "40") (name "Net-(C1-Pad1)") (class "Default")
      (node (ref "C1") (pin "1") (pinfunction "1_1") (pintype "input"))
      (node (ref "C2") (pin "2") (pinfunction "2_2") (pintype "input"))
      (node (ref "L1") (pin "2") (pinfunction "2_2") (pintype "unspecified"))
      (node (ref "R4") (pin "2") (pinfunction "2_2") (pintype "unspecified"))
    )
    (net (code "41") (name "Net-(C11-Pad2)") (class "Default")
      (node (ref "C11") (pin "2") (pinfunction "2_2") (pintype "input"))
      (node (ref "R8") (pin "1") (pinfunction "1_1") (pintype "input"))
    )
    (net (code "42") (name "Net-(C12-Pad2)") (class "Default")
      (node (ref "C12") (pin "2") (pinfunction "2_2") (pintype "input"))
      (node (ref "R9") (pin "1") (pinfunction "1_1") (pintype "input"))
    )
    (net (code "43") (name "Net-(C16-Pad2)") (class "Default")
      (node (ref "C16") (pin "2") (pinfunction "2_2") (pintype "input"))
      (node (ref "R10") (pin "1") (pinfunction "1_1") (pintype "input"))
    )
    (net (code "44") (name "Net-(C17-Pad2)") (class "Default")
      (node (ref "C17") (pin "2") (pinfunction "2_2") (pintype "input"))
      (node (ref "R11") (pin "1") (pinfunction "1_1") (pintype "input"))
    )
    (net (code "45") (name "Net-(D1-Pad1)") (class "Default")
      (node (ref "D1") (pin "1") (pinfunction "1_1") (pintype "unspecified"))
      (node (ref "F1") (pin "2") (pinfunction "2_2") (pintype "unspecified"))
    )
    (net (code "46") (name "Net-(D2-A)") (class "Default")
      (node (ref "D2") (pin "1") (pinfunction "A_1") (pintype "unspecified"))
      (node (ref "L2") (pin "1") (pinfunction "1_1") (pintype "unspecified"))
      (node (ref "U1") (pin "1") (pinfunction "SW_1") (pintype "input"))
    )
    (net (code "47") (name "Net-(D3-K)") (class "Default")
      (node (ref "C21") (pin "2") (pinfunction "2_2") (pintype "input"))
      (node (ref "C4") (pin "2") (pinfunction "2_2") (pintype "input"))
      (node (ref "D3") (pin "2") (pinfunction "K_2") (pintype "unspecified"))
      (node (ref "D4") (pin "2") (pinfunction "K_2") (pintype "unspecified"))
      (node (ref "L2") (pin "2") (pinfunction "2_2") (pintype "unspecified"))
      (node (ref "U1") (pin "4") (pinfunction "EN_4") (pintype "input"))
      (node (ref "U1") (pin "5") (pinfunction "IN_5") (pintype "input"))
    )
    (net (code "48") (name "Net-(L1-Pad1)") (class "Default")
      (node (ref "L1") (pin "1") (pinfunction "1_1") (pintype "unspecified"))
      (node (ref "MIC1") (pin "1") (pinfunction "1_1") (pintype "input"))
    )
    (net (code "49") (name "Net-(LED0-K)") (class "Default")
      (node (ref "LED0") (pin "1") (pinfunction "K_1") (pintype "input"))
      (node (ref "R14") (pin "2") (pinfunction "2_2") (pintype "input"))
    )
    (net (code "50") (name "Net-(LED1-K)") (class "Default")
      (node (ref "LED1") (pin "1") (pinfunction "K_1") (pintype "input"))
      (node (ref "R15") (pin "2") (pinfunction "2_2") (pintype "input"))
    )
    (net (code "51") (name "Net-(LED2-K)") (class "Default")
      (node (ref "LED2") (pin "1") (pinfunction "K_1") (pintype "input"))
      (node (ref "R1") (pin "2") (pinfunction "2_2") (pintype "input"))
    )
    (net (code "52") (name "Net-(LED3-K)") (class "Default")
      (node (ref "LED3") (pin "1") (pinfunction "K_1") (pintype "input"))
      (node (ref "R2") (pin "2") (pinfunction "2_2") (pintype "input"))
    )
    (net (code "53") (name "Net-(R16-Pad2)") (class "Default")
      (node (ref "R16") (pin "2") (pinfunction "2_2") (pintype "input"))
      (node (ref "SW2") (pin "1") (pinfunction "1_1") (pintype "input"))
    )
    (net (code "54") (name "Net-(R17-Pad2)") (class "Default")
      (node (ref "R17") (pin "2") (pinfunction "2_2") (pintype "input"))
      (node (ref "SW3") (pin "1") (pinfunction "1_1") (pintype "input"))
    )
    (net (code "55") (name "Net-(R18-Pad2)") (class "Default")
      (node (ref "R18") (pin "2") (pinfunction "2_2") (pintype "input"))
      (node (ref "SW4") (pin "1") (pinfunction "1_1") (pintype "input"))
    )
    (net (code "56") (name "Net-(R19-Pad2)") (class "Default")
      (node (ref "R19") (pin "2") (pinfunction "2_2") (pintype "input"))
      (node (ref "SW5") (pin "1") (pinfunction "1_1") (pintype "input"))
    )
    (net (code "57") (name "Net-(R20-Pad2)") (class "Default")
      (node (ref "R20") (pin "2") (pinfunction "2_2") (pintype "input"))
      (node (ref "SW6") (pin "1") (pinfunction "1_1") (pintype "input"))
    )
    (net (code "58") (name "Net-(SW9-Pad4)") (class "Default")
      (node (ref "SW9") (pin "4") (pinfunction "4_4") (pintype "unspecified"))
      (node (ref "U8") (pin "1") (pinfunction "1_1") (pintype "unspecified"))
    )
    (net (code "59") (name "Net-(U1-FB)") (class "Default")
      (node (ref "R6") (pin "1") (pinfunction "1_1") (pintype "input"))
      (node (ref "R7") (pin "2") (pinfunction "2_2") (pintype "input"))
      (node (ref "U1") (pin "3") (pinfunction "FB_3") (pintype "input"))
    )
    (net (code "60") (name "Net-(U3-BYPASS)") (class "Default")
      (node (ref "C8") (pin "1") (pinfunction "1_1") (pintype "input"))
      (node (ref "U3") (pin "2") (pinfunction "BYPASS_2") (pintype "unspecified"))
    )
    (net (code "61") (name "Net-(U3-IN+)") (class "Default")
      (node (ref "R9") (pin "2") (pinfunction "2_2") (pintype "input"))
      (node (ref "U3") (pin "4") (pinfunction "IN+_4") (pintype "unspecified"))
    )
    (net (code "62") (name "Net-(U3-IN-)") (class "Default")
      (node (ref "R8") (pin "2") (pinfunction "2_2") (pintype "input"))
      (node (ref "U3") (pin "3") (pinfunction "IN-_3") (pintype "unspecified"))
    )
    (net (code "63") (name "Net-(U4-BYPASS)") (class "Default")
      (node (ref "C13") (pin "1") (pinfunction "1_1") (pintype "input"))
      (node (ref "U4") (pin "2") (pinfunction "BYPASS_2") (pintype "unspecified"))
    )
    (net (code "64") (name "Net-(U4-IN+)") (class "Default")
      (node (ref "R11") (pin "2") (pinfunction "2_2") (pintype "input"))
      (node (ref "U4") (pin "4") (pinfunction "IN+_4") (pintype "unspecified"))
    )
    (net (code "65") (name "Net-(U4-IN-)") (class "Default")
      (node (ref "R10") (pin "2") (pinfunction "2_2") (pintype "input"))
      (node (ref "U4") (pin "3") (pinfunction "IN-_3") (pintype "unspecified"))
    )
    (net (code "66") (name "Net-(USB1-CC1)") (class "Default")
      (node (ref "R3") (pin "1") (pinfunction "1_1") (pintype "input"))
      (node (ref "USB1") (pin "4") (pinfunction "CC1_4") (pintype "unspecified"))
    )
    (net (code "67") (name "Net-(USB1-CC2)") (class "Default")
      (node (ref "R5") (pin "1") (pinfunction "1_1") (pintype "input"))
      (node (ref "USB1") (pin "10") (pinfunction "CC2_10") (pintype "unspecified"))
    )
    (net (code "68") (name "PGND") (class "Default")
      (node (ref "C20") (pin "1") (pinfunction "1_1") (pintype "input"))
      (node (ref "C5") (pin "1") (pinfunction "1_1") (pintype "input"))
      (node (ref "R13") (pin "1") (pinfunction "1_1") (pintype "input"))
      (node (ref "R7") (pin "1") (pinfunction "1_1") (pintype "input"))
      (node (ref "U1") (pin "2") (pinfunction "GND_2") (pintype "input"))
    )
    (net (code "69") (name "VBAT+") (class "Default")
      (node (ref "C19") (pin "2") (pinfunction "2_2") (pintype "input"))
      (node (ref "C7") (pin "2") (pinfunction "2_2") (pintype "unspecified"))
      (node (ref "D3") (pin "1") (pinfunction "A_1") (pintype "unspecified"))
      (node (ref "H2") (pin "1") (pinfunction "1_1") (pintype "input"))
      (node (ref "LED3") (pin "2") (pinfunction "A_2") (pintype "input"))
      (node (ref "SW10") (pin "4") (pinfunction "4_4") (pintype "unspecified"))
      (node (ref "SW9") (pin "2") (pinfunction "2_2") (pintype "unspecified"))
      (node (ref "U2") (pin "25") (pinfunction "VBAT_25") (pintype "input"))
      (node (ref "U7") (pin "3") (pinfunction "VIN_3") (pintype "unspecified"))
    )
    (net (code "70") (name "VBUS") (class "Default")
      (node (ref "C22") (pin "2") (pinfunction "2_2") (pintype "unspecified"))
      (node (ref "D4") (pin "1") (pinfunction "A_1") (pintype "unspecified"))
      (node (ref "F1") (pin "1") (pinfunction "1_1") (pintype "unspecified"))
      (node (ref "H2") (pin "2") (pinfunction "2_2") (pintype "input"))
      (node (ref "LED2") (pin "2") (pinfunction "A_2") (pintype "input"))
      (node (ref "U2") (pin "26") (pinfunction "VCHG_26") (pintype "input"))
    )
    (net (code "71") (name "unconnected-(AE1-Pad2)") (class "Default")
      (node (ref "AE1") (pin "2") (pinfunction "2_2") (pintype "input"))
    )
    (net (code "72") (name "unconnected-(SW1-Pad3)") (class "Default")
      (node (ref "SW1") (pin "3") (pinfunction "3_3") (pintype "input"))
    )
    (net (code "73") (name "unconnected-(SW1-Pad4)") (class "Default")
      (node (ref "SW1") (pin "4") (pinfunction "4_4") (pintype "input"))
    )
    (net (code "74") (name "unconnected-(SW2-Pad3)") (class "Default")
      (node (ref "SW2") (pin "3") (pinfunction "3_3") (pintype "input"))
    )
    (net (code "75") (name "unconnected-(SW2-Pad4)") (class "Default")
      (node (ref "SW2") (pin "4") (pinfunction "4_4") (pintype "input"))
    )
    (net (code "76") (name "unconnected-(SW3-Pad3)") (class "Default")
      (node (ref "SW3") (pin "3") (pinfunction "3_3") (pintype "input"))
    )
    (net (code "77") (name "unconnected-(SW3-Pad4)") (class "Default")
      (node (ref "SW3") (pin "4") (pinfunction "4_4") (pintype "input"))
    )
    (net (code "78") (name "unconnected-(SW4-Pad3)") (class "Default")
      (node (ref "SW4") (pin "3") (pinfunction "3_3") (pintype "input"))
    )
    (net (code "79") (name "unconnected-(SW4-Pad4)") (class "Default")
      (node (ref "SW4") (pin "4") (pinfunction "4_4") (pintype "input"))
    )
    (net (code "80") (name "unconnected-(SW5-Pad3)") (class "Default")
      (node (ref "SW5") (pin "3") (pinfunction "3_3") (pintype "input"))
    )
    (net (code "81") (name "unconnected-(SW5-Pad4)") (class "Default")
      (node (ref "SW5") (pin "4") (pinfunction "4_4") (pintype "input"))
    )
    (net (code "82") (name "unconnected-(SW6-Pad3)") (class "Default")
      (node (ref "SW6") (pin "3") (pinfunction "3_3") (pintype "input"))
    )
    (net (code "83") (name "unconnected-(SW6-Pad4)") (class "Default")
      (node (ref "SW6") (pin "4") (pinfunction "4_4") (pintype "input"))
    )
    (net (code "84") (name "unconnected-(SW9-Pad1)") (class "Default")
      (node (ref "SW9") (pin "1") (pinfunction "1_1") (pintype "unspecified"))
    )
    (net (code "85") (name "unconnected-(SW9-Pad3)") (class "Default")
      (node (ref "SW9") (pin "3") (pinfunction "3_3") (pintype "unspecified"))
    )
    (net (code "86") (name "unconnected-(SW9-Pad5)") (class "Default")
      (node (ref "SW9") (pin "5") (pinfunction "5_5") (pintype "unspecified"))
    )
    (net (code "87") (name "unconnected-(SW9-Pad6)") (class "Default")
      (node (ref "SW9") (pin "6") (pinfunction "6_6") (pintype "unspecified"))
    )
    (net (code "88") (name "unconnected-(SW10-Pad5)") (class "Default")
      (node (ref "SW10") (pin "5") (pinfunction "5_5") (pintype "unspecified"))
    )
    (net (code "89") (name "unconnected-(SW10-Pad6)") (class "Default")
      (node (ref "SW10") (pin "6") (pinfunction "6_6") (pintype "unspecified"))
    )
    (net (code "90") (name "unconnected-(U1-NC-Pad6)") (class "Default")
      (node (ref "U1") (pin "6") (pinfunction "NC_6") (pintype "input+no_connect"))
    )
    (net (code "91") (name "unconnected-(U2-1V8-Pad22)") (class "Default")
      (node (ref "U2") (pin "22") (pinfunction "1V8_22") (pintype "input+no_connect"))
    )
    (net (code "92") (name "unconnected-(U2-LED2-Pad18)") (class "Default")
      (node (ref "U2") (pin "18") (pinfunction "LED2_18") (pintype "input+no_connect"))
    )
    (net (code "93") (name "unconnected-(U7-TAB-Pad4)") (class "Default")
      (node (ref "U7") (pin "4") (pinfunction "TAB_4") (pintype "unspecified+no_connect"))
    )
    (net (code "94") (name "unconnected-(USB1-SBU1-Pad9)") (class "Default")
      (node (ref "USB1") (pin "9") (pinfunction "SBU1_9") (pintype "unspecified+no_connect"))
    )
    (net (code "95") (name "unconnected-(USB1-SBU2-Pad3)") (class "Default")
      (node (ref "USB1") (pin "3") (pinfunction "SBU2_3") (pintype "unspecified+no_connect"))
    )
  )
)
